# esquema_TTH_v03_filled.net
KiCad netlist of a schematic drawn in EAGLE
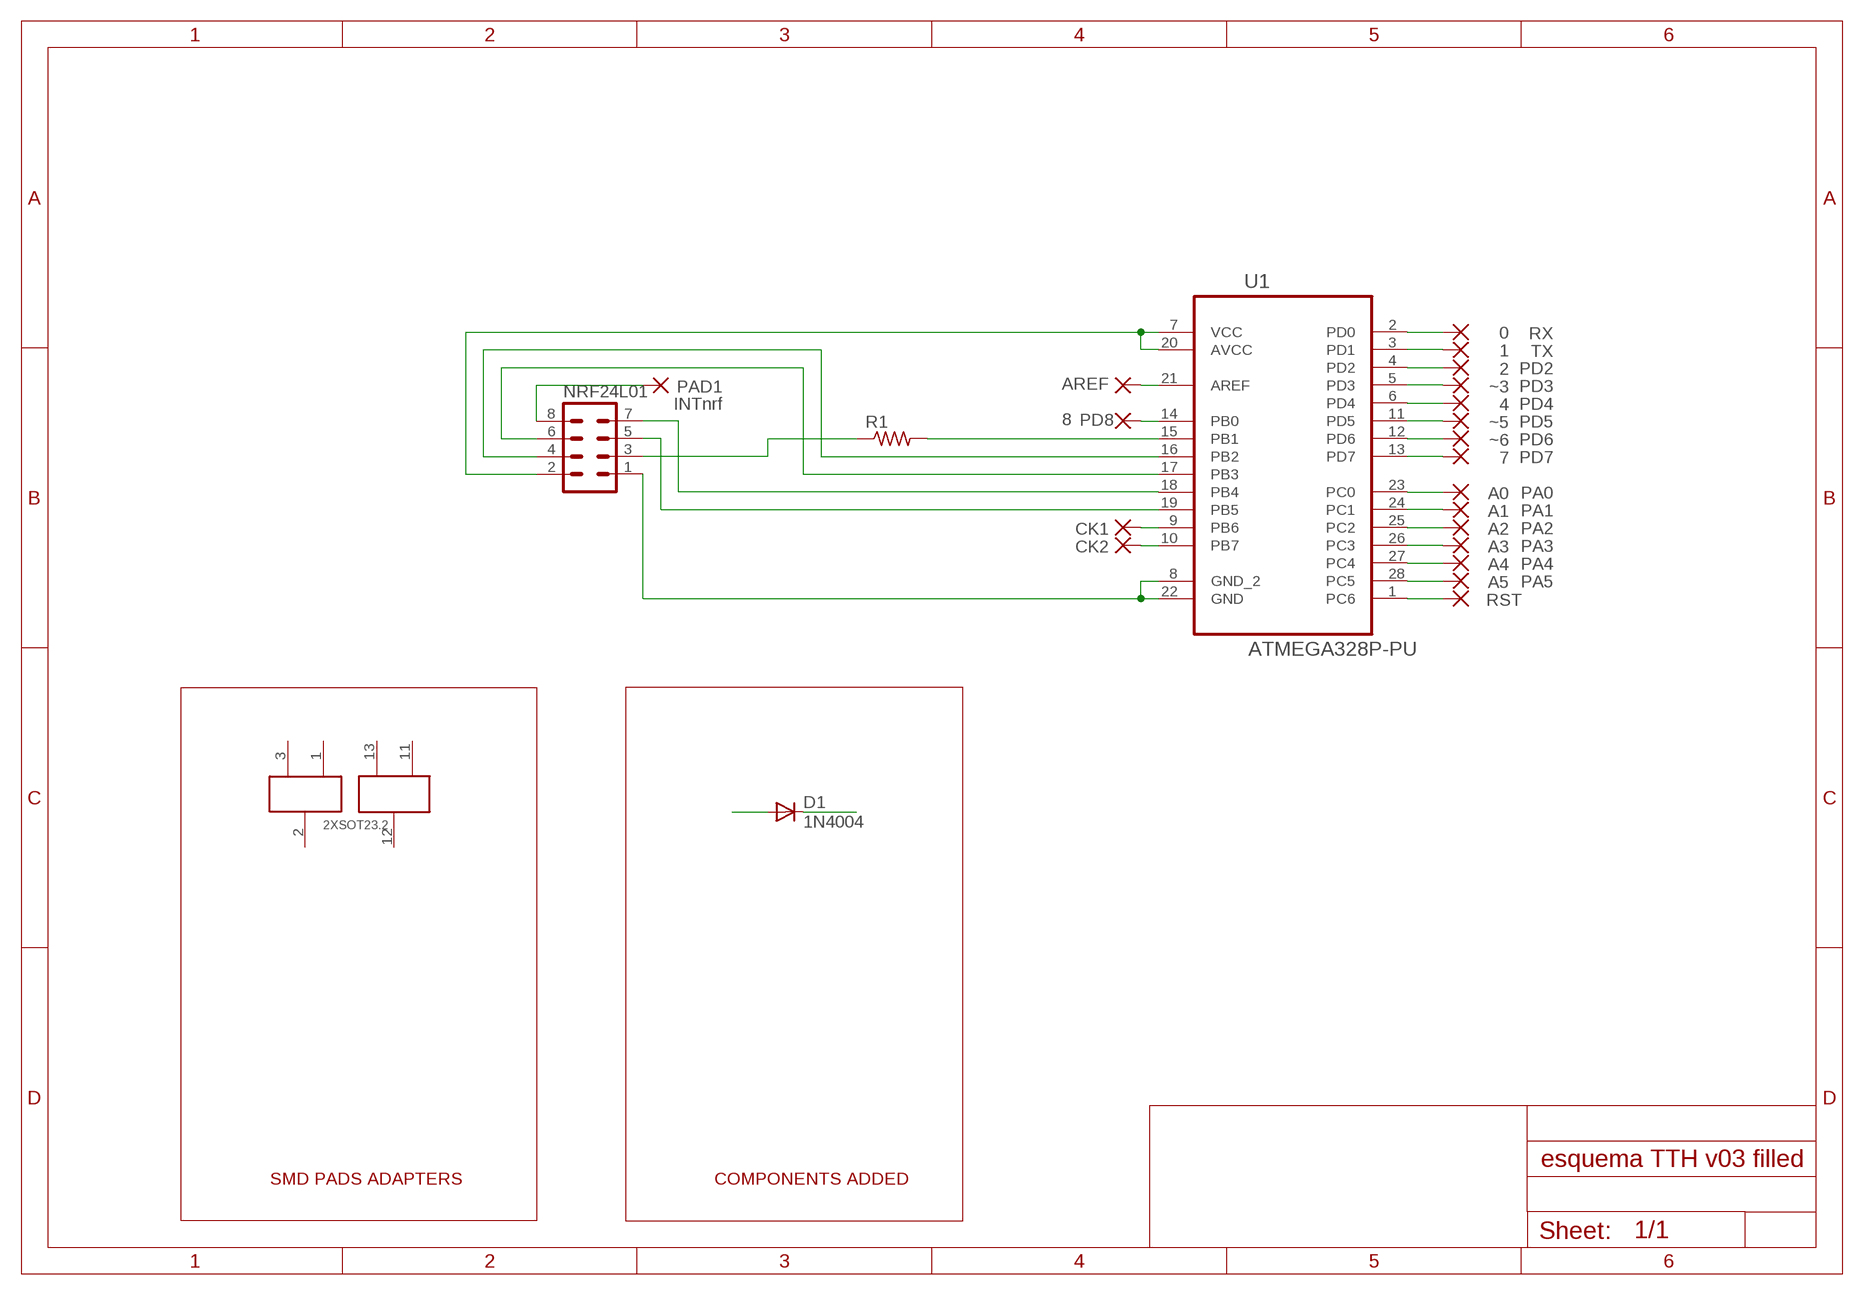
[diagram p0: schematic, sheet 1]

(export (version "E")
  (design (tool "Eeschema 10.0.6"))
  (components
    (comp (ref "2")
      (value "PD2")
      (footprint "eagle-import:2,15_1,0")
      (libsource (lib "eagle-import") (part "2,15/1,0"))
    )
    (comp (ref "4")
      (value "PD4")
      (footprint "eagle-import:2,15_1,0")
      (libsource (lib "eagle-import") (part "2,15/1,0"))
    )
    (comp (ref "7")
      (value "PD7")
      (footprint "eagle-import:2,15_1,0")
      (libsource (lib "eagle-import") (part "2,15/1,0"))
    )
    (comp (ref "8")
      (value "PD8")
      (footprint "eagle-import:2,15_1,0")
      (libsource (lib "eagle-import") (part "2,15/1,0"))
    )
    (comp (ref "A0")
      (value "PA0")
      (footprint "eagle-import:2,15_1,0")
      (libsource (lib "eagle-import") (part "2,15/1,0"))
    )
    (comp (ref "A1")
      (value "PA1")
      (footprint "eagle-import:2,15_1,0")
      (libsource (lib "eagle-import") (part "2,15/1,0"))
    )
    (comp (ref "A2")
      (value "PA2")
      (footprint "eagle-import:2,15_1,0")
      (libsource (lib "eagle-import") (part "2,15/1,0"))
    )
    (comp (ref "A3")
      (value "PA3")
      (footprint "eagle-import:2,15_1,0")
      (libsource (lib "eagle-import") (part "2,15/1,0"))
    )
    (comp (ref "A4")
      (value "PA4")
      (footprint "eagle-import:2,15_1,0")
      (libsource (lib "eagle-import") (part "2,15/1,0"))
    )
    (comp (ref "A5")
      (value "PA5")
      (footprint "eagle-import:2,15_1,0")
      (libsource (lib "eagle-import") (part "2,15/1,0"))
    )
    (comp (ref "AREF")
      (value "2,15/1,0")
      (footprint "eagle-import:2,15_1,0")
      (libsource (lib "eagle-import") (part "2,15/1,0"))
    )
    (comp (ref "CK1")
      (value "2,15/1,0")
      (footprint "eagle-import:2,15_1,0")
      (libsource (lib "eagle-import") (part "2,15/1,0"))
    )
    (comp (ref "CK2")
      (value "2,15/1,0")
      (footprint "eagle-import:2,15_1,0")
      (libsource (lib "eagle-import") (part "2,15/1,0"))
    )
    (comp (ref "D1")
      (value "1N4004")
      (footprint "eagle-import:DO41-10")
      (libsource (lib "eagle-import") (part "1N4004"))
    )
    (comp (ref "NRF24L01")
      (value "MA04-2")
      (footprint "eagle-import:MA04-2")
      (libsource (lib "eagle-import") (part "MA04-2"))
    )
    (comp (ref "PAD1")
      (value "INTnrf")
      (footprint "eagle-import:2,15_1,0")
      (libsource (lib "eagle-import") (part "2,15/1,0"))
    )
    (comp (ref "R1")
      (value "R-US_0207/10")
      (footprint "eagle-import:0207_10")
      (libsource (lib "eagle-import") (part "R-US_0207/10"))
    )
    (comp (ref "RST")
      (value "2,15/1,0")
      (footprint "eagle-import:2,15_1,0")
      (libsource (lib "eagle-import") (part "2,15/1,0"))
    )
    (comp (ref "RX")
      (value "0")
      (footprint "eagle-import:2,15_1,0")
      (libsource (lib "eagle-import") (part "2,15/1,0"))
    )
    (comp (ref "TX")
      (value "1")
      (footprint "eagle-import:2,15_1,0")
      (libsource (lib "eagle-import") (part "2,15/1,0"))
    )
    (comp (ref "U$2")
      (value "2XSOT23.2")
      (footprint "eagle-import:SOT23.5")
      (libsource (lib "eagle-import") (part "2XSOT23.2"))
    )
    (comp (ref "U1")
      (value "ATMEGA328P-PU")
      (footprint "eagle-import:DIP254P762X457-28")
      (libsource (lib "eagle-import") (part "ATMEGA328P-PU"))
    )
    (comp (ref "~3")
      (value "PD3")
      (footprint "eagle-import:2,15_1,0")
      (libsource (lib "eagle-import") (part "2,15/1,0"))
    )
    (comp (ref "~5")
      (value "PD5")
      (footprint "eagle-import:2,15_1,0")
      (libsource (lib "eagle-import") (part "2,15/1,0"))
    )
    (comp (ref "~6")
      (value "PD6")
      (footprint "eagle-import:2,15_1,0")
      (libsource (lib "eagle-import") (part "2,15/1,0"))
    )
  )
  (nets
    (net (code "1") (name "Net-(2-P)") (class "Default")
      (node (ref "2") (pin "1") (pinfunction "P_1") (pintype "passive"))
      (node (ref "U1") (pin "4") (pinfunction "PD2_4") (pintype "bidirectional"))
    )
    (net (code "2") (name "Net-(4-P)") (class "Default")
      (node (ref "4") (pin "1") (pinfunction "P_1") (pintype "passive"))
      (node (ref "U1") (pin "6") (pinfunction "PD4_6") (pintype "bidirectional"))
    )
    (net (code "3") (name "Net-(7-P)") (class "Default")
      (node (ref "7") (pin "1") (pinfunction "P_1") (pintype "passive"))
      (node (ref "U1") (pin "13") (pinfunction "PD7_13") (pintype "bidirectional"))
    )
    (net (code "4") (name "Net-(8-P)") (class "Default")
      (node (ref "8") (pin "1") (pinfunction "P_1") (pintype "passive"))
      (node (ref "U1") (pin "14") (pinfunction "PB0_14") (pintype "bidirectional"))
    )
    (net (code "5") (name "Net-(A0-P)") (class "Default")
      (node (ref "A0") (pin "1") (pinfunction "P_1") (pintype "passive"))
      (node (ref "U1") (pin "23") (pinfunction "PC0_23") (pintype "bidirectional"))
    )
    (net (code "6") (name "Net-(A1-P)") (class "Default")
      (node (ref "A1") (pin "1") (pinfunction "P_1") (pintype "passive"))
      (node (ref "U1") (pin "24") (pinfunction "PC1_24") (pintype "bidirectional"))
    )
    (net (code "7") (name "Net-(A2-P)") (class "Default")
      (node (ref "A2") (pin "1") (pinfunction "P_1") (pintype "passive"))
      (node (ref "U1") (pin "25") (pinfunction "PC2_25") (pintype "bidirectional"))
    )
    (net (code "8") (name "Net-(A3-P)") (class "Default")
      (node (ref "A3") (pin "1") (pinfunction "P_1") (pintype "passive"))
      (node (ref "U1") (pin "26") (pinfunction "PC3_26") (pintype "bidirectional"))
    )
    (net (code "9") (name "Net-(A4-P)") (class "Default")
      (node (ref "A4") (pin "1") (pinfunction "P_1") (pintype "passive"))
      (node (ref "U1") (pin "27") (pinfunction "PC4_27") (pintype "bidirectional"))
    )
    (net (code "10") (name "Net-(A5-P)") (class "Default")
      (node (ref "A5") (pin "1") (pinfunction "P_1") (pintype "passive"))
      (node (ref "U1") (pin "28") (pinfunction "PC5_28") (pintype "bidirectional"))
    )
    (net (code "11") (name "Net-(AREF-P)") (class "Default")
      (node (ref "AREF") (pin "1") (pinfunction "P_1") (pintype "passive"))
      (node (ref "U1") (pin "21") (pinfunction "AREF_21") (pintype "input"))
    )
    (net (code "12") (name "Net-(CK1-P)") (class "Default")
      (node (ref "CK1") (pin "1") (pinfunction "P_1") (pintype "passive"))
      (node (ref "U1") (pin "9") (pinfunction "PB6_9") (pintype "bidirectional"))
    )
    (net (code "13") (name "Net-(CK2-P)") (class "Default")
      (node (ref "CK2") (pin "1") (pinfunction "P_1") (pintype "passive"))
      (node (ref "U1") (pin "10") (pinfunction "PB7_10") (pintype "bidirectional"))
    )
    (net (code "14") (name "Net-(NRF24L01-Pad3)") (class "Default")
      (node (ref "NRF24L01") (pin "3") (pinfunction "3_3") (pintype "passive"))
      (node (ref "R1") (pin "1") (pinfunction "1_1") (pintype "passive"))
    )
    (net (code "15") (name "Net-(PAD1-P)") (class "Default")
      (node (ref "NRF24L01") (pin "8") (pinfunction "8_8") (pintype "passive"))
      (node (ref "PAD1") (pin "1") (pinfunction "P_1") (pintype "passive"))
    )
    (net (code "16") (name "Net-(RST-P)") (class "Default")
      (node (ref "RST") (pin "1") (pinfunction "P_1") (pintype "passive"))
      (node (ref "U1") (pin "1") (pinfunction "PC6_1") (pintype "bidirectional"))
    )
    (net (code "17") (name "Net-(RX-P)") (class "Default")
      (node (ref "RX") (pin "1") (pinfunction "P_1") (pintype "passive"))
      (node (ref "U1") (pin "2") (pinfunction "PD0_2") (pintype "bidirectional"))
    )
    (net (code "18") (name "Net-(TX-P)") (class "Default")
      (node (ref "TX") (pin "1") (pinfunction "P_1") (pintype "passive"))
      (node (ref "U1") (pin "3") (pinfunction "PD1_3") (pintype "bidirectional"))
    )
    (net (code "19") (name "Net-(U1-AVCC)") (class "Default")
      (node (ref "NRF24L01") (pin "2") (pinfunction "2_2") (pintype "passive"))
      (node (ref "U1") (pin "20") (pinfunction "AVCC_20") (pintype "power_in"))
      (node (ref "U1") (pin "7") (pinfunction "VCC_7") (pintype "power_in"))
    )
    (net (code "20") (name "Net-(U1-GND)") (class "Default")
      (node (ref "NRF24L01") (pin "1") (pinfunction "1_1") (pintype "passive"))
      (node (ref "U1") (pin "22") (pinfunction "GND_22") (pintype "passive"))
      (node (ref "U1") (pin "8") (pinfunction "GND_2_8") (pintype "passive"))
    )
    (net (code "21") (name "Net-(U1-PB1)") (class "Default")
      (node (ref "R1") (pin "2") (pinfunction "2_2") (pintype "passive"))
      (node (ref "U1") (pin "15") (pinfunction "PB1_15") (pintype "bidirectional"))
    )
    (net (code "22") (name "Net-(U1-PB2)") (class "Default")
      (node (ref "NRF24L01") (pin "4") (pinfunction "4_4") (pintype "passive"))
      (node (ref "U1") (pin "16") (pinfunction "PB2_16") (pintype "bidirectional"))
    )
    (net (code "23") (name "Net-(U1-PB3)") (class "Default")
      (node (ref "NRF24L01") (pin "6") (pinfunction "6_6") (pintype "passive"))
      (node (ref "U1") (pin "17") (pinfunction "PB3_17") (pintype "bidirectional"))
    )
    (net (code "24") (name "Net-(U1-PB4)") (class "Default")
      (node (ref "NRF24L01") (pin "7") (pinfunction "7_7") (pintype "passive"))
      (node (ref "U1") (pin "18") (pinfunction "PB4_18") (pintype "bidirectional"))
    )
    (net (code "25") (name "Net-(U1-PB5)") (class "Default")
      (node (ref "NRF24L01") (pin "5") (pinfunction "5_5") (pintype "passive"))
      (node (ref "U1") (pin "19") (pinfunction "PB5_19") (pintype "bidirectional"))
    )
    (net (code "26") (name "Net-(U1-PD3)") (class "Default")
      (node (ref "U1") (pin "5") (pinfunction "PD3_5") (pintype "bidirectional"))
      (node (ref "~3") (pin "1") (pinfunction "P_1") (pintype "passive"))
    )
    (net (code "27") (name "Net-(U1-PD5)") (class "Default")
      (node (ref "U1") (pin "11") (pinfunction "PD5_11") (pintype "bidirectional"))
      (node (ref "~5") (pin "1") (pinfunction "P_1") (pintype "passive"))
    )
    (net (code "28") (name "Net-(U1-PD6)") (class "Default")
      (node (ref "U1") (pin "12") (pinfunction "PD6_12") (pintype "bidirectional"))
      (node (ref "~6") (pin "1") (pinfunction "P_1") (pintype "passive"))
    )
    (net (code "29") (name "unconnected-(D1-PadA)") (class "Default")
      (node (ref "D1") (pin "A") (pinfunction "A_A") (pintype "passive"))
    )
    (net (code "30") (name "unconnected-(D1-PadC)") (class "Default")
      (node (ref "D1") (pin "C") (pinfunction "C_C") (pintype "passive"))
    )
    (net (code "31") (name "unconnected-(U$2-Pad1)") (class "Default")
      (node (ref "U$2") (pin "1") (pinfunction "1_1") (pintype "bidirectional"))
    )
    (net (code "32") (name "unconnected-(U$2-Pad2)") (class "Default")
      (node (ref "U$2") (pin "2") (pinfunction "2_2") (pintype "bidirectional"))
    )
    (net (code "33") (name "unconnected-(U$2-Pad3)") (class "Default")
      (node (ref "U$2") (pin "3") (pinfunction "3_3") (pintype "bidirectional"))
    )
    (net (code "34") (name "unconnected-(U$2-Pad11)") (class "Default")
      (node (ref "U$2") (pin "11") (pinfunction "11_11") (pintype "bidirectional"))
    )
    (net (code "35") (name "unconnected-(U$2-Pad12)") (class "Default")
      (node (ref "U$2") (pin "12") (pinfunction "12_12") (pintype "bidirectional"))
    )
    (net (code "36") (name "unconnected-(U$2-Pad13)") (class "Default")
      (node (ref "U$2") (pin "13") (pinfunction "13_13") (pintype "bidirectional"))
    )
  )
)
